# Sensors.net
KiCad netlist of a schematic drawn in Altium Designer
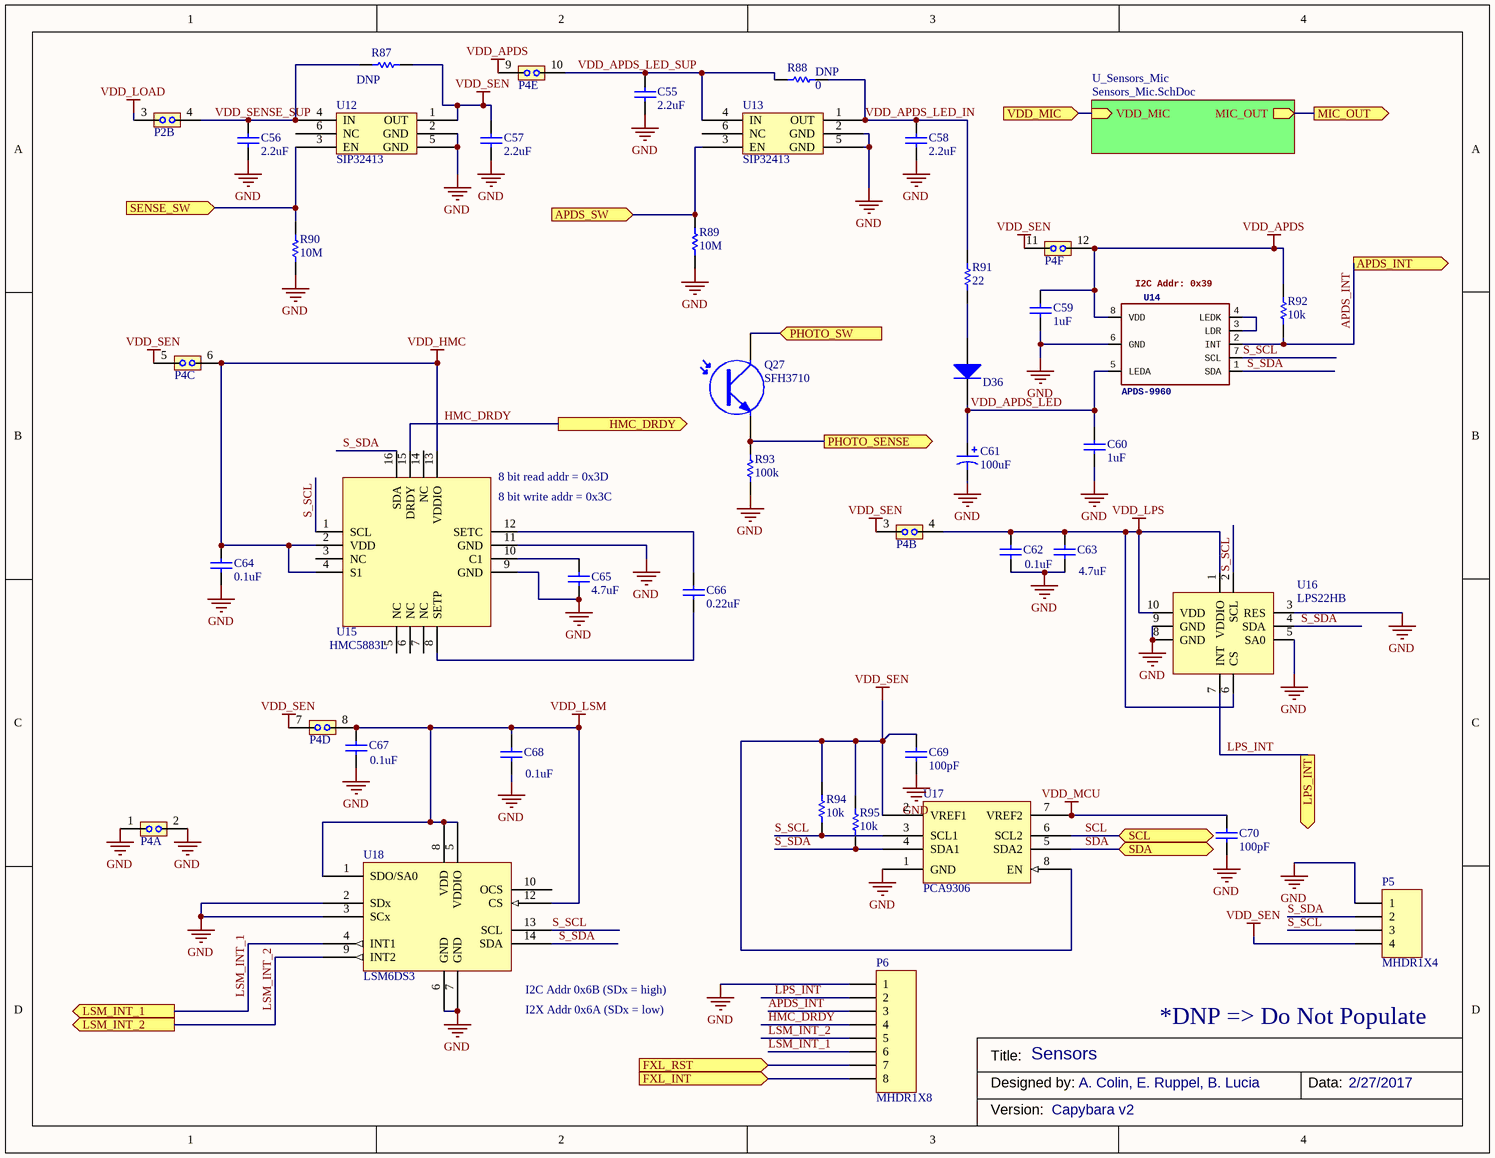
[diagram p0: Sensors.SchDoc]

(export (version "E")
  (design (tool "Eeschema 10.0.6"))
  (components
    (comp (ref "C55")
      (value "2.2uF")
      (footprint "0603")
      (description "Ceramic Capacitor (Surface Mount)")
      (fields
        (field (name "MANUFACTURER") "Murata Electronics North America")
        (field (name "MANUFACTURER PART NUMBER") "GRM188R61C225KE15D")
      )
      (libsource (lib "DRP_Basic_2014") (part "Cap"))
    )
    (comp (ref "C56")
      (value "2.2uF")
      (footprint "0603")
      (description "Ceramic Capacitor (Surface Mount)")
      (fields
        (field (name "MANUFACTURER") "Murata Electronics North America")
        (field (name "MANUFACTURER PART NUMBER") "GRM188R61C225KE15D")
      )
      (libsource (lib "DRP_Basic_2014") (part "Cap"))
    )
    (comp (ref "C57")
      (value "2.2uF")
      (footprint "0603")
      (description "Ceramic Capacitor (Surface Mount)")
      (fields
        (field (name "MANUFACTURER") "Murata Electronics North America")
        (field (name "MANUFACTURER PART NUMBER") "GRM188R61C225KE15D")
      )
      (libsource (lib "DRP_Basic_2014") (part "Cap"))
    )
    (comp (ref "C58")
      (value "2.2uF")
      (footprint "0603")
      (description "Ceramic Capacitor (Surface Mount)")
      (fields
        (field (name "MANUFACTURER") "Murata Electronics North America")
        (field (name "MANUFACTURER PART NUMBER") "GRM188R61C225KE15D")
      )
      (libsource (lib "DRP_Basic_2014") (part "Cap"))
    )
    (comp (ref "C59")
      (value "1uF")
      (footprint "0603")
      (description "Ceramic Capacitor (Surface Mount)")
      (fields
        (field (name "MANUFACTURER") "Murata Electronics North America")
        (field (name "MANUFACTURER PART NUMBER") "GRM188R61A105KA61D")
      )
      (libsource (lib "DRP_Basic_2014") (part "Cap"))
    )
    (comp (ref "C60")
      (value "1uF")
      (footprint "0603")
      (description "Ceramic Capacitor (Surface Mount)")
      (fields
        (field (name "MANUFACTURER") "Murata Electronics North America")
        (field (name "MANUFACTURER PART NUMBER") "GRM188R61A105KA61D")
      )
      (libsource (lib "DRP_Basic_2014") (part "Cap"))
    )
    (comp (ref "C61")
      (value "100uF")
      (footprint "0805")
      (description "Polarized Capacitor")
      (fields
        (field (name "MANUFACTURER PART NUMBER") "GRM21BR60G107ME15L")
        (field (name "MANUFACTURER") "Murata Electronics North America")
      )
      (libsource (lib "DRP_Basic_2014") (part "Cap - Polarized"))
    )
    (comp (ref "C62")
      (value "0.1uF")
      (footprint "0603")
      (description "Ceramic Capacitor (Surface Mount)")
      (fields
        (field (name "MANUFACTURER") "Murata Electronics North America")
        (field (name "MANUFACTURER PART NUMBER") "GRM188R71C104KA01D")
      )
      (libsource (lib "DRP_Basic_2014") (part "Cap"))
    )
    (comp (ref "C63")
      (value "4.7uF")
      (footprint "0603")
      (description "Ceramic Capacitor (Surface Mount)")
      (fields
        (field (name "MANUFACTURER") "Samsung Electro-Mechanics")
        (field (name "MANUFACTURER PART NUMBER") "CL10B475KQ8NQNC")
      )
      (libsource (lib "DRP_Basic_2014") (part "Cap"))
    )
    (comp (ref "C64")
      (value "0.1uF")
      (footprint "0603")
      (description "Ceramic Capacitor (Surface Mount)")
      (fields
        (field (name "MANUFACTURER") "Murata Electronics North America")
        (field (name "MANUFACTURER PART NUMBER") "GRM188R71C104KA01D")
      )
      (libsource (lib "DRP_Basic_2014") (part "Cap"))
    )
    (comp (ref "C65")
      (value "4.7uF")
      (footprint "0603")
      (description "CAP CER 4.7UF 4V X6S")
      (fields
        (field (name "MANUFACTURER") "Samsung Electro-Mechanics")
        (field (name "MANUFACTURER PART NUMBER") "CL10B475KQ8NQNC")
      )
      (libsource (lib "DRP_Basic_2014") (part "Cap"))
    )
    (comp (ref "C66")
      (value "0.22uF")
      (footprint "0603")
      (description "Ceramic Capacitor (Surface Mount)")
      (fields
        (field (name "MANUFACTURER") "Murata Electronics North America")
        (field (name "MANUFACTURER PART NUMBER") "GRM188R71E224KA88D")
      )
      (libsource (lib "DRP_Basic_2014") (part "Cap"))
    )
    (comp (ref "C67")
      (value "0.1uF")
      (footprint "0603")
      (description "Ceramic Capacitor (Surface Mount)")
      (fields
        (field (name "MANUFACTURER") "Murata Electronics North America")
        (field (name "MANUFACTURER PART NUMBER") "GRM188R71C104KA01D")
      )
      (libsource (lib "DRP_Basic_2014") (part "Cap"))
    )
    (comp (ref "C68")
      (value "0.1uF")
      (footprint "0603")
      (description "Ceramic Capacitor (Surface Mount)")
      (fields
        (field (name "MANUFACTURER") "Murata Electronics North America")
        (field (name "MANUFACTURER PART NUMBER") "GRM188R71C104KA01D")
      )
      (libsource (lib "DRP_Basic_2014") (part "Cap"))
    )
    (comp (ref "C69")
      (value "100pF")
      (footprint "0603")
      (description "Ceramic Capacitor (Surface Mount)")
      (fields
        (field (name "MANUFACTURER") "Kemet")
        (field (name "MANUFACTURER PART NUMBER") "C0603C101J5GACTU")
      )
      (libsource (lib "DRP_Basic_2014") (part "Cap"))
    )
    (comp (ref "C70")
      (value "100pF")
      (footprint "0603")
      (description "Ceramic Capacitor (Surface Mount)")
      (fields
        (field (name "MANUFACTURER") "Kemet")
        (field (name "MANUFACTURER PART NUMBER") "C0603C101J5GACTU")
      )
      (libsource (lib "DRP_Basic_2014") (part "Cap"))
    )
    (comp (ref "D36")
      (value "Diode")
      (footprint "SOD-523")
      (description "General Purpose Diode")
      (fields
        (field (name "MANUFACTURER") "Vishay Semiconductor")
        (field (name "MANUFACTURER PART NUMBER") "BAS40-02V-V-G-08")
      )
      (libsource (lib "DRP_Basic_2014") (part "Diode"))
    )
    (comp (ref "P2") (value "JMPHDR_8") (footprint "MHDR2X8") (libsource (lib "Sprite") (part "JMPHDR_8")))
    (comp (ref "P4")
      (value "JMPHDR_6")
      (footprint "MHDR2X6")
      (fields
        (field (name "DIGI-KEY PART NUMBER") "S9015E-06-ND")
        (field (name "MANUFACTURER") "Sullins Connector Solutions")
        (field (name "MANUFACTURER PART NUMBER") "GRPB062VWVN-RC")
      )
      (libsource (lib "") (part "JMPHDR_6_2"))
    )
    (comp (ref "P5")
      (value "MHDR1X4")
      (footprint "MHDR1X4")
      (description "Header, 4-Pin")
      (fields
        (field (name "DIGI-KEY PART NUMBER") "952-3358-ND")
        (field (name "DISTRIBUTOR PART NUMBER") "855-M52-5000445")
        (field (name "PUBLISHER") "Altium Limited")
      )
      (libsource (lib "Miscellaneous Connectors") (part "MHDR1X4"))
    )
    (comp (ref "P6")
      (value "MHDR1X8")
      (footprint "MHDR1X8")
      (description "Header, 8-Pin")
      (fields
        (field (name "DIGI-KEY PART NUMBER") "952-3361-ND")
        (field (name "DISTRIBUTOR PART NUMBER") "855-M52-5000845")
        (field (name "PUBLISHER") "Altium Limited")
      )
      (libsource (lib "Miscellaneous Connectors") (part "MHDR1X8"))
    )
    (comp (ref "Q27")
      (value "SFH3710")
      (footprint "0805-W")
      (description "NPN Phototransistor")
      (fields
        (field (name "DIGI-KEY PART NUMBER") "475-1268-1-ND")
        (field (name "MANUFACTURER") "OSRAM Opto Semiconductors Inc")
      )
      (libsource (lib "DRP_Basic_2014") (part "Photo NPN"))
    )
    (comp (ref "R87")
      (value "Res")
      (footprint "0603")
      (description "Chip Resistor (Surface Mount)")
      (fields
        (field (name "MANUFACTURER") "Yageo")
        (field (name "MANUFACTURER PART NUMBER") "RC0603JR-070RL")
        (field (name "NOTE") "DNP")
      )
      (libsource (lib "DRP_Basic_2014") (part "Res"))
    )
    (comp (ref "R88")
      (value "0")
      (footprint "0603")
      (description "Chip Resistor (Surface Mount)")
      (fields
        (field (name "MANUFACTURER") "Yageo")
        (field (name "MANUFACTURER PART NUMBER") "RC0603JR-070RL")
        (field (name "NOTE") "DNP")
      )
      (libsource (lib "DRP_Basic_2014") (part "Res"))
    )
    (comp (ref "R89")
      (value "10M")
      (footprint "0603")
      (description "Chip Resistor (Surface Mount)")
      (fields
        (field (name "MANUFACTURER") "Yageo")
        (field (name "MANUFACTURER PART NUMBER") "RC0603JR-0710ML")
      )
      (libsource (lib "DRP_Basic_2014") (part "Res"))
    )
    (comp (ref "R90")
      (value "10M")
      (footprint "0603")
      (description "Chip Resistor (Surface Mount)")
      (fields
        (field (name "MANUFACTURER") "Yageo")
        (field (name "MANUFACTURER PART NUMBER") "RC0603JR-0710ML")
      )
      (libsource (lib "DRP_Basic_2014") (part "Res"))
    )
    (comp (ref "R91")
      (value "22")
      (footprint "0603")
      (description "Chip Resistor (Surface Mount)")
      (fields
        (field (name "MANUFACTURER") "Vishay Beyschlag")
        (field (name "MANUFACTURER PART NUMBER") "MCT06030C2209FP500")
      )
      (libsource (lib "DRP_Basic_2014") (part "Res"))
    )
    (comp (ref "R92")
      (value "10k")
      (footprint "0603")
      (description "Chip Resistor (Surface Mount)")
      (fields
        (field (name "MANUFACTURER") "Yageo")
        (field (name "MANUFACTURER PART NUMBER") "RC0603FR-0710KL")
      )
      (libsource (lib "DRP_Basic_2014") (part "Res"))
    )
    (comp (ref "R93")
      (value "100k")
      (footprint "0603")
      (description "Chip Resistor (Surface Mount)")
      (fields
        (field (name "MANUFACTURER") "Yageo")
        (field (name "MANUFACTURER PART NUMBER") "RT0603FRE07100KL")
      )
      (libsource (lib "DRP_Basic_2014") (part "Res"))
    )
    (comp (ref "R94")
      (value "10k")
      (footprint "0603")
      (description "Chip Resistor (Surface Mount)")
      (fields
        (field (name "MANUFACTURER") "Yageo")
        (field (name "MANUFACTURER PART NUMBER") "RC0603FR-0710KL")
      )
      (libsource (lib "DRP_Basic_2014") (part "Res"))
    )
    (comp (ref "R95")
      (value "10k")
      (footprint "0603")
      (description "Chip Resistor (Surface Mount)")
      (fields
        (field (name "MANUFACTURER") "Yageo")
        (field (name "MANUFACTURER PART NUMBER") "RC0603FR-0710KL")
      )
      (libsource (lib "DRP_Basic_2014") (part "Res"))
    )
    (comp (ref "U12")
      (value "SIP32413")
      (footprint "SC70-6")
      (fields
        (field (name "DIGI-KEY PART NUMBER") "SIP32431DR3-T1GE3CT-ND")
        (field (name "DISTRIBUTOR PART NUMBER") "781-SIP32431DR3-GE3")
        (field (name "MANUFACTURER") "Vishay Semiconductors")
      )
      (libsource (lib "Sprite") (part "SIP32431"))
    )
    (comp (ref "U13")
      (value "SIP32413")
      (footprint "SC70-6")
      (fields
        (field (name "DIGI-KEY PART NUMBER") "SIP32431DR3-T1GE3CT-ND")
        (field (name "DISTRIBUTOR PART NUMBER") "781-SIP32431DR3-GE3")
        (field (name "MANUFACTURER") "Vishay Semiconductors")
      )
      (libsource (lib "Sprite") (part "SIP32431"))
    )
    (comp (ref "U14")
      (value "APDS-9960")
      (footprint "DFN_APDS_v2")
      (description "Avago APDS-9960 digital proximity, ambient light, RGB, and gesture sensor.")
      (fields
        (field (name "DIGI-KEY PART NUMBER") "516-3480-1-ND")
        (field (name "DISTRIBUTOR PART NUMBER") "630-APDS-9960")
      )
      (libsource (lib "SparkFun-Sensors") (part "APDS-9960"))
    )
    (comp (ref "U15")
      (value "HMC5883L")
      (footprint "SPARKFUN_16LPCC-DUP")
      (description "IC COMPASS 3 AXIS I2C 16LCC SMD")
      (fields
        (field (name "MANUFACTURER") "Honeywell")
        (field (name "MANUFACTURER PART NUMBER") "HMC5883L-TR")
      )
      (libsource (lib "EDB_Lib") (part "HMC5883L"))
    )
    (comp (ref "U16")
      (value "LPS22HB")
      (footprint "HLGA-10L")
      (fields
        (field (name "DIGI-KEY PART NUMBER") "497-16265-1-ND")
        (field (name "DISTRIBUTOR PART NUMBER") "511-LPS22HBTR")
        (field (name "MANUFACTURER") "STMicroelectronics")
      )
      (libsource (lib "Sprite") (part "LPS22HB"))
    )
    (comp (ref "U17")
      (value "PCA9306")
      (footprint "8-VFSOP")
      (description "I2C Level Shifter")
      (fields
        (field (name "MANUFACTURER PART NUMBER") "PCA9306DCURG4")
        (field (name "DIGI-KEY PART NUMBER") "296-46174-1-ND")
      )
      (libsource (lib "Sprite") (part "PCA9306"))
    )
    (comp (ref "U18")
      (value "LSM6DS3")
      (footprint "LGA-14")
      (fields
        (field (name "NAME") "LSM6DS3")
        (field (name "DISTRIBUTOR PART NUMBER") "511-LSM6DS3TR")
        (field (name "MANUFACTURER") "ST Microelectronics")
        (field (name "MANUFACTURER PART NUMBER") "LSM6DS3TR")
      )
      (libsource (lib "Sprite") (part "LSM6DS3"))
    )
  )
  (nets
    (net (code "1") (name "/APDS_INT") (class "Default")
      (node (ref "P6") (pin "3") (pinfunction "3_3") (pintype "passive"))
      (node (ref "R92") (pin "1") (pinfunction "1_1") (pintype "passive"))
      (node (ref "U14") (pin "2") (pinfunction "INT_2") (pintype "passive"))
    )
    (net (code "2") (name "/APDS_SW") (class "Default")
      (node (ref "R89") (pin "2") (pinfunction "2_2") (pintype "passive"))
      (node (ref "U13") (pin "3") (pinfunction "EN_3") (pintype "passive"))
    )
    (net (code "3") (name "/FXL_INT") (class "Default")
      (node (ref "P6") (pin "8") (pinfunction "8_8") (pintype "passive"))
    )
    (net (code "4") (name "/FXL_RST") (class "Default")
      (node (ref "P6") (pin "7") (pinfunction "7_7") (pintype "passive"))
    )
    (net (code "5") (name "/HMC_DRDY") (class "Default")
      (node (ref "P6") (pin "4") (pinfunction "4_4") (pintype "passive"))
      (node (ref "U15") (pin "15") (pinfunction "DRDY_15") (pintype "passive"))
    )
    (net (code "6") (name "/LPS_INT") (class "Default")
      (node (ref "P6") (pin "2") (pinfunction "2_2") (pintype "passive"))
      (node (ref "U16") (pin "7") (pinfunction "INT_7") (pintype "passive"))
    )
    (net (code "7") (name "/LSM_INT_1") (class "Default")
      (node (ref "P6") (pin "6") (pinfunction "6_6") (pintype "passive"))
      (node (ref "U18") (pin "4") (pinfunction "INT1_4") (pintype "output"))
    )
    (net (code "8") (name "/LSM_INT_2") (class "Default")
      (node (ref "P6") (pin "5") (pinfunction "5_5") (pintype "passive"))
      (node (ref "U18") (pin "9") (pinfunction "INT2_9") (pintype "output"))
    )
    (net (code "10") (name "/PHOTO_SENSE") (class "Default")
      (node (ref "Q27") (pin "2") (pinfunction "E_2") (pintype "passive"))
      (node (ref "R93") (pin "2") (pinfunction "2_2") (pintype "passive"))
    )
    (net (code "11") (name "/PHOTO_SW") (class "Default")
      (node (ref "Q27") (pin "1") (pinfunction "C_1") (pintype "passive"))
    )
    (net (code "12") (name "/SCL") (class "Default")
      (node (ref "U17") (pin "6") (pinfunction "SCL2_6") (pintype "open_collector"))
    )
    (net (code "13") (name "/SDA") (class "Default")
      (node (ref "U17") (pin "5") (pinfunction "SDA2_5") (pintype "open_collector"))
    )
    (net (code "14") (name "/SENSE_SW") (class "Default")
      (node (ref "R90") (pin "2") (pinfunction "2_2") (pintype "passive"))
      (node (ref "U12") (pin "3") (pinfunction "EN_3") (pintype "passive"))
    )
    (net (code "15") (name "/S_SCL") (class "Default")
      (node (ref "P5") (pin "3") (pinfunction "3_3") (pintype "passive"))
      (node (ref "R94") (pin "1") (pinfunction "1_1") (pintype "passive"))
      (node (ref "U14") (pin "7") (pinfunction "SCL_7") (pintype "passive"))
      (node (ref "U15") (pin "1") (pinfunction "SCL_1") (pintype "passive"))
      (node (ref "U16") (pin "2") (pinfunction "SCL_2") (pintype "passive"))
      (node (ref "U17") (pin "3") (pinfunction "SCL1_3") (pintype "open_collector"))
      (node (ref "U18") (pin "13") (pinfunction "SCL_13") (pintype "passive"))
    )
    (net (code "16") (name "/S_SDA") (class "Default")
      (node (ref "P5") (pin "2") (pinfunction "2_2") (pintype "passive"))
      (node (ref "R95") (pin "1") (pinfunction "1_1") (pintype "passive"))
      (node (ref "U14") (pin "1") (pinfunction "SDA_1") (pintype "passive"))
      (node (ref "U15") (pin "16") (pinfunction "SDA_16") (pintype "passive"))
      (node (ref "U16") (pin "4") (pinfunction "SDA_4") (pintype "passive"))
      (node (ref "U17") (pin "4") (pinfunction "SDA1_4") (pintype "open_collector"))
      (node (ref "U18") (pin "14") (pinfunction "SDA_14") (pintype "passive"))
    )
    (net (code "17") (name "/VDD_APDS_LED") (class "Default")
      (node (ref "C60") (pin "2") (pinfunction "2_2") (pintype "passive"))
      (node (ref "C61") (pin "1") (pinfunction "1_1") (pintype "passive"))
      (node (ref "D36") (pin "2") (pinfunction "C_2") (pintype "passive"))
      (node (ref "U14") (pin "5") (pinfunction "LEDA_5") (pintype "passive"))
    )
    (net (code "18") (name "/VDD_APDS_LED_IN") (class "Default")
      (node (ref "C58") (pin "2") (pinfunction "2_2") (pintype "passive"))
      (node (ref "R88") (pin "2") (pinfunction "2_2") (pintype "passive"))
      (node (ref "R91") (pin "2") (pinfunction "2_2") (pintype "passive"))
      (node (ref "U13") (pin "1") (pinfunction "OUT_1") (pintype "passive"))
    )
    (net (code "19") (name "/VDD_APDS_LED_SUP") (class "Default")
      (node (ref "C55") (pin "2") (pinfunction "2_2") (pintype "passive"))
      (node (ref "P4") (pin "10") (pinfunction "10_10") (pintype "passive"))
      (node (ref "R88") (pin "1") (pinfunction "1_1") (pintype "passive"))
      (node (ref "U13") (pin "4") (pinfunction "IN_4") (pintype "passive"))
    )
    (net (code "21") (name "/VDD_SENSE_SUP") (class "Default")
      (node (ref "C56") (pin "2") (pinfunction "2_2") (pintype "passive"))
      (node (ref "P2") (pin "4") (pinfunction "4_4") (pintype "passive"))
      (node (ref "R87") (pin "1") (pinfunction "1_1") (pintype "passive"))
      (node (ref "U12") (pin "4") (pinfunction "IN_4") (pintype "passive"))
    )
    (net (code "22") (name "GND") (class "Default")
      (node (ref "C55") (pin "1") (pinfunction "1_1") (pintype "passive"))
      (node (ref "C56") (pin "1") (pinfunction "1_1") (pintype "passive"))
      (node (ref "C57") (pin "1") (pinfunction "1_1") (pintype "passive"))
      (node (ref "C58") (pin "1") (pinfunction "1_1") (pintype "passive"))
      (node (ref "C59") (pin "1") (pinfunction "1_1") (pintype "passive"))
      (node (ref "C60") (pin "1") (pinfunction "1_1") (pintype "passive"))
      (node (ref "C61") (pin "2") (pinfunction "2_2") (pintype "passive"))
      (node (ref "C62") (pin "2") (pinfunction "2_2") (pintype "passive"))
      (node (ref "C63") (pin "2") (pinfunction "2_2") (pintype "passive"))
      (node (ref "C64") (pin "2") (pinfunction "2_2") (pintype "passive"))
      (node (ref "C65") (pin "2") (pinfunction "2_2") (pintype "passive"))
      (node (ref "C67") (pin "2") (pinfunction "2_2") (pintype "passive"))
      (node (ref "C68") (pin "2") (pinfunction "2_2") (pintype "passive"))
      (node (ref "C69") (pin "1") (pinfunction "1_1") (pintype "passive"))
      (node (ref "C70") (pin "1") (pinfunction "1_1") (pintype "passive"))
      (node (ref "P4") (pin "1") (pinfunction "1_1") (pintype "passive"))
      (node (ref "P4") (pin "2") (pinfunction "2_2") (pintype "passive"))
      (node (ref "P5") (pin "1") (pinfunction "1_1") (pintype "passive"))
      (node (ref "P6") (pin "1") (pinfunction "1_1") (pintype "passive"))
      (node (ref "R89") (pin "1") (pinfunction "1_1") (pintype "passive"))
      (node (ref "R90") (pin "1") (pinfunction "1_1") (pintype "passive"))
      (node (ref "R93") (pin "1") (pinfunction "1_1") (pintype "passive"))
      (node (ref "U12") (pin "2") (pinfunction "GND_2") (pintype "passive"))
      (node (ref "U12") (pin "5") (pinfunction "GND_5") (pintype "passive"))
      (node (ref "U13") (pin "2") (pinfunction "GND_2") (pintype "passive"))
      (node (ref "U13") (pin "5") (pinfunction "GND_5") (pintype "passive"))
      (node (ref "U14") (pin "6") (pinfunction "GND_6") (pintype "passive"))
      (node (ref "U15") (pin "11") (pinfunction "GND_11") (pintype "passive"))
      (node (ref "U15") (pin "9") (pinfunction "GND_9") (pintype "passive"))
      (node (ref "U16") (pin "3") (pinfunction "RES_3") (pintype "passive"))
      (node (ref "U16") (pin "5") (pinfunction "SA0_5") (pintype "passive"))
      (node (ref "U16") (pin "8") (pinfunction "GND_8") (pintype "passive"))
      (node (ref "U16") (pin "9") (pinfunction "GND_9") (pintype "passive"))
      (node (ref "U17") (pin "1") (pinfunction "GND_1") (pintype "power_in"))
      (node (ref "U18") (pin "2") (pinfunction "SDx_2") (pintype "passive"))
      (node (ref "U18") (pin "3") (pinfunction "SCx_3") (pintype "passive"))
      (node (ref "U18") (pin "6") (pinfunction "GND_6") (pintype "power_in"))
      (node (ref "U18") (pin "7") (pinfunction "GND_7") (pintype "power_in"))
    )
    (net (code "23") (name "Net-(D36-A)") (class "Default")
      (node (ref "D36") (pin "1") (pinfunction "A_1") (pintype "passive"))
      (node (ref "R91") (pin "1") (pinfunction "1_1") (pintype "passive"))
    )
    (net (code "24") (name "Net-(U14-LDR)") (class "Default")
      (node (ref "U14") (pin "3") (pinfunction "LDR_3") (pintype "passive"))
      (node (ref "U14") (pin "4") (pinfunction "LEDK_4") (pintype "passive"))
    )
    (net (code "25") (name "Net-(U15-C1)") (class "Default")
      (node (ref "C65") (pin "1") (pinfunction "1_1") (pintype "passive"))
      (node (ref "U15") (pin "10") (pinfunction "C1_10") (pintype "passive"))
    )
    (net (code "26") (name "Net-(U15-SETC)") (class "Default")
      (node (ref "C66") (pin "2") (pinfunction "2_2") (pintype "passive"))
      (node (ref "U15") (pin "12") (pinfunction "SETC_12") (pintype "passive"))
    )
    (net (code "27") (name "Net-(U15-SETP)") (class "Default")
      (node (ref "C66") (pin "1") (pinfunction "1_1") (pintype "passive"))
      (node (ref "U15") (pin "8") (pinfunction "SETP_8") (pintype "passive"))
    )
    (net (code "28") (name "VDD_APDS") (class "Default")
      (node (ref "C59") (pin "2") (pinfunction "2_2") (pintype "passive"))
      (node (ref "P4") (pin "12") (pinfunction "12_12") (pintype "passive"))
      (node (ref "P4") (pin "9") (pinfunction "9_9") (pintype "passive"))
      (node (ref "R92") (pin "2") (pinfunction "2_2") (pintype "passive"))
      (node (ref "U14") (pin "8") (pinfunction "VDD_8") (pintype "passive"))
    )
    (net (code "29") (name "VDD_HMC") (class "Default")
      (node (ref "C64") (pin "1") (pinfunction "1_1") (pintype "passive"))
      (node (ref "P4") (pin "6") (pinfunction "6_6") (pintype "passive"))
      (node (ref "U15") (pin "13") (pinfunction "VDDIO_13") (pintype "passive"))
      (node (ref "U15") (pin "2") (pinfunction "VDD_2") (pintype "passive"))
      (node (ref "U15") (pin "4") (pinfunction "S1_4") (pintype "passive"))
    )
    (net (code "30") (name "VDD_LOAD") (class "Default")
      (node (ref "P2") (pin "3") (pinfunction "3_3") (pintype "passive"))
    )
    (net (code "31") (name "VDD_LPS") (class "Default")
      (node (ref "C62") (pin "1") (pinfunction "1_1") (pintype "passive"))
      (node (ref "C63") (pin "1") (pinfunction "1_1") (pintype "passive"))
      (node (ref "P4") (pin "4") (pinfunction "4_4") (pintype "passive"))
      (node (ref "U16") (pin "1") (pinfunction "VDDIO_1") (pintype "passive"))
      (node (ref "U16") (pin "10") (pinfunction "VDD_10") (pintype "passive"))
      (node (ref "U16") (pin "6") (pinfunction "CS_6") (pintype "passive"))
    )
    (net (code "32") (name "VDD_LSM") (class "Default")
      (node (ref "C67") (pin "1") (pinfunction "1_1") (pintype "passive"))
      (node (ref "C68") (pin "1") (pinfunction "1_1") (pintype "passive"))
      (node (ref "P4") (pin "8") (pinfunction "8_8") (pintype "passive"))
      (node (ref "U18") (pin "1") (pinfunction "SDO/SA0_1") (pintype "passive"))
      (node (ref "U18") (pin "12") (pinfunction "CS_12") (pintype "input"))
      (node (ref "U18") (pin "5") (pinfunction "VDDIO_5") (pintype "passive"))
      (node (ref "U18") (pin "8") (pinfunction "VDD_8") (pintype "passive"))
    )
    (net (code "33") (name "VDD_MCU") (class "Default")
      (node (ref "C70") (pin "2") (pinfunction "2_2") (pintype "passive"))
      (node (ref "U17") (pin "7") (pinfunction "VREF2_7") (pintype "power_in"))
    )
    (net (code "34") (name "VDD_SEN") (class "Default")
      (node (ref "C57") (pin "2") (pinfunction "2_2") (pintype "passive"))
      (node (ref "C69") (pin "2") (pinfunction "2_2") (pintype "passive"))
      (node (ref "P4") (pin "11") (pinfunction "11_11") (pintype "passive"))
      (node (ref "P4") (pin "3") (pinfunction "3_3") (pintype "passive"))
      (node (ref "P4") (pin "5") (pinfunction "5_5") (pintype "passive"))
      (node (ref "P4") (pin "7") (pinfunction "7_7") (pintype "passive"))
      (node (ref "P5") (pin "4") (pinfunction "4_4") (pintype "passive"))
      (node (ref "R87") (pin "2") (pinfunction "2_2") (pintype "passive"))
      (node (ref "R94") (pin "2") (pinfunction "2_2") (pintype "passive"))
      (node (ref "R95") (pin "2") (pinfunction "2_2") (pintype "passive"))
      (node (ref "U12") (pin "1") (pinfunction "OUT_1") (pintype "passive"))
      (node (ref "U17") (pin "2") (pinfunction "VREF1_2") (pintype "power_in"))
      (node (ref "U17") (pin "8") (pinfunction "EN_8") (pintype "input"))
    )
    (net (code "35") (name "unconnected-(U12-NC-Pad6)") (class "Default")
      (node (ref "U12") (pin "6") (pinfunction "NC_6") (pintype "passive"))
    )
    (net (code "36") (name "unconnected-(U13-NC-Pad6)") (class "Default")
      (node (ref "U13") (pin "6") (pinfunction "NC_6") (pintype "passive"))
    )
    (net (code "37") (name "unconnected-(U15-NC-Pad3)") (class "Default")
      (node (ref "U15") (pin "3") (pinfunction "NC_3") (pintype "passive"))
    )
    (net (code "38") (name "unconnected-(U15-NC-Pad5)") (class "Default")
      (node (ref "U15") (pin "5") (pinfunction "NC_5") (pintype "passive"))
    )
    (net (code "39") (name "unconnected-(U15-NC-Pad6)") (class "Default")
      (node (ref "U15") (pin "6") (pinfunction "NC_6") (pintype "passive"))
    )
    (net (code "40") (name "unconnected-(U15-NC-Pad7)") (class "Default")
      (node (ref "U15") (pin "7") (pinfunction "NC_7") (pintype "passive"))
    )
    (net (code "41") (name "unconnected-(U15-NC-Pad14)") (class "Default")
      (node (ref "U15") (pin "14") (pinfunction "NC_14") (pintype "passive"))
    )
    (net (code "42") (name "unconnected-(U18-OCS-Pad10)") (class "Default")
      (node (ref "U18") (pin "10") (pinfunction "OCS_10") (pintype "passive"))
    )
  )
)
